# sch_pet.net
KiCad netlist of a schematic drawn in Altium Designer
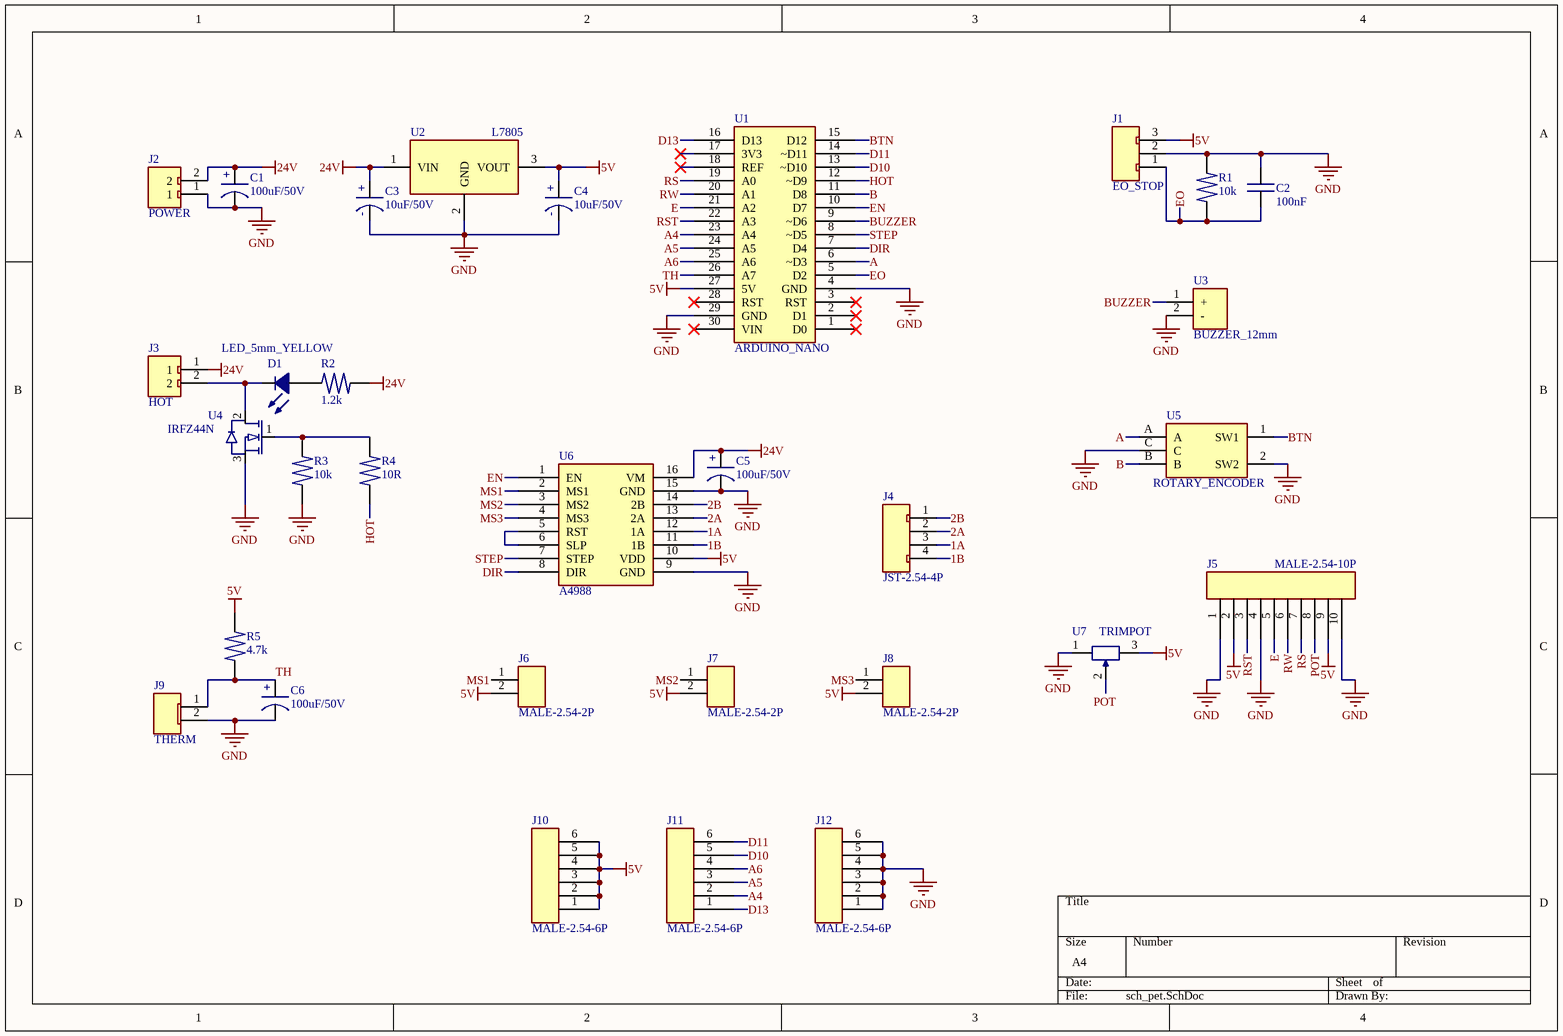
[diagram p0: sch_pet.SchDoc]

(export (version "E")
  (design (tool "Eeschema 10.0.6"))
  (components
    (comp (ref "C1")
      (value "100uF/50V")
      (footprint "100uF/50V")
      (description "Electrolytic Capacitor 100uF/50V")
      (libsource (lib "Electrolytic Capacitor") (part "100uF/50V"))
    )
    (comp (ref "C2")
      (value "100nF")
      (footprint "CAPACITOR 104")
      (description "Ceramic Capacitor 104, 3mm.")
      (libsource (lib "Ceramic Capacitor") (part "CAPACITOR 104"))
    )
    (comp (ref "C3")
      (value "10uF/50V")
      (footprint "10uF/50V")
      (description "Electrolytic Capacitor 10uF/50V")
      (libsource (lib "Electrolytic Capacitor") (part "10uF/50V"))
    )
    (comp (ref "C4")
      (value "10uF/50V")
      (footprint "10uF/50V")
      (description "Electrolytic Capacitor 10uF/50V")
      (libsource (lib "Electrolytic Capacitor") (part "10uF/50V"))
    )
    (comp (ref "C5")
      (value "100uF/50V")
      (footprint "100uF/50V")
      (description "Electrolytic Capacitor 100uF/50V")
      (libsource (lib "Electrolytic Capacitor") (part "100uF/50V"))
    )
    (comp (ref "C6")
      (value "100uF/50V")
      (footprint "100uF/50V")
      (description "Electrolytic Capacitor 100uF/50V")
      (libsource (lib "Electrolytic Capacitor") (part "100uF/50V"))
    )
    (comp (ref "D1")
      (value "LED_5mm_YELLOW")
      (footprint "LED_5mm_YELLOW")
      (description "LED PTH 5mm Yellow.")
      (libsource (lib "LED") (part "LED_5mm_YELLOW"))
    )
    (comp (ref "J1")
      (value "EO_STOP")
      (footprint "JST-2.54-3P")
      (description "Female Connector JST 3 Vias, 2.54mm.")
      (libsource (lib "Connectors") (part "JST-2.54-3P"))
    )
    (comp (ref "J2")
      (value "POWER")
      (footprint "BORNE-5.00-2P")
      (description "Borne 2 Vias, Pitch 5mm.")
      (libsource (lib "Connectors") (part "BORNE-5.00-2P"))
    )
    (comp (ref "J3")
      (value "HOT")
      (footprint "BORNE-5.00-2P")
      (description "Borne 2 Vias, Pitch 5mm.")
      (libsource (lib "") (part "BORNE-5.00-2P_1"))
    )
    (comp (ref "J4")
      (value "JST-2.54-4P")
      (footprint "JST-2.54-4P")
      (description "Female Connector JST 4 Vias, 2.54mm.")
      (libsource (lib "Connectors") (part "JST-2.54-4P"))
    )
    (comp (ref "J5")
      (value "MALE-2.54-10P")
      (footprint "MALE-2.54-10P")
      (description "Male Header Connector 2.54mm 10 Pins.")
      (libsource (lib "Connectors") (part "MALE-2.54-10P"))
    )
    (comp (ref "J6")
      (value "MALE-2.54-2P")
      (footprint "MALE-2.54-2P")
      (description "Male Header Connector 2.54mm 2 Pins.")
      (libsource (lib "Connectors") (part "MALE-2.54-2P"))
    )
    (comp (ref "J7")
      (value "MALE-2.54-2P")
      (footprint "MALE-2.54-2P")
      (description "Male Header Connector 2.54mm 2 Pins.")
      (libsource (lib "Connectors") (part "MALE-2.54-2P"))
    )
    (comp (ref "J8")
      (value "MALE-2.54-2P")
      (footprint "MALE-2.54-2P")
      (description "Male Header Connector 2.54mm 2 Pins.")
      (libsource (lib "Connectors") (part "MALE-2.54-2P"))
    )
    (comp (ref "J9")
      (value "THERM")
      (footprint "JST-2.54-2P")
      (description "Female Connector JST 2 Vias, 2.54mm.")
      (libsource (lib "Connectors") (part "JST-2.54-2P"))
    )
    (comp (ref "J10")
      (value "MALE-2.54-6P")
      (footprint "MALE-2.54-6P")
      (description "Male Header Connector 2.54mm 6 Pins.")
      (libsource (lib "Connectors") (part "MALE-2.54-6P"))
    )
    (comp (ref "J11")
      (value "MALE-2.54-6P")
      (footprint "MALE-2.54-6P")
      (description "Male Header Connector 2.54mm 6 Pins.")
      (libsource (lib "Connectors") (part "MALE-2.54-6P"))
    )
    (comp (ref "J12")
      (value "MALE-2.54-6P")
      (footprint "MALE-2.54-6P")
      (description "Male Header Connector 2.54mm 6 Pins.")
      (libsource (lib "Connectors") (part "MALE-2.54-6P"))
    )
    (comp (ref "R1")
      (value "10k")
      (footprint "RESISTOR_PTH_9.5mm")
      (description "Generic Resistor 9.5mm.")
      (libsource (lib "Resistors") (part "RESISTOR_9.5mm"))
    )
    (comp (ref "R2")
      (value "1.2k")
      (footprint "RESISTOR_PTH_9.5mm")
      (description "Generic Resistor 9.5mm.")
      (libsource (lib "Resistors") (part "RESISTOR_9.5mm"))
    )
    (comp (ref "R3")
      (value "10k")
      (footprint "RESISTOR_PTH_9.5mm")
      (description "Generic Resistor 9.5mm.")
      (libsource (lib "Resistors") (part "RESISTOR_9.5mm"))
    )
    (comp (ref "R4")
      (value "10R")
      (footprint "RESISTOR_PTH_9.5mm")
      (description "Generic Resistor 9.5mm.")
      (libsource (lib "Resistors") (part "RESISTOR_9.5mm"))
    )
    (comp (ref "R5")
      (value "4.7k")
      (footprint "RESISTOR_PTH_9.5mm")
      (description "Generic Resistor 9.5mm.")
      (libsource (lib "Resistors") (part "RESISTOR_9.5mm"))
    )
    (comp (ref "U1")
      (value "ARDUINO_NANO")
      (footprint "ARDUINO_NANO")
      (description "Based on ATmega328P, Clock 16MHz, Flash 32KB, 14 Digital Pins, 8 Analog Pins, 5V, Vin 7-12V.")
      (libsource (lib "Arduino") (part "ARDUINO_NANO"))
    )
    (comp (ref "U2")
      (value "L7805")
      (footprint "L7805_180")
      (description "IC REG LINEAR 5V 1.5A TO220AB")
      (libsource (lib "Voltage Regulators") (part "L7805"))
    )
    (comp (ref "U3")
      (value "BUZZER_12mm")
      (footprint "BUZZER_12mm")
      (description "BUZZER MAGNETIC 12MM")
      (libsource (lib "Random") (part "BUZZER_12mm"))
    )
    (comp (ref "U4")
      (value "IRFZ44N")
      (footprint "IRFZ44N")
      (description "55V N-CHANNEL MOSFET TO-220-3")
      (libsource (lib "Transistors") (part "IRFZ44N"))
    )
    (comp (ref "U5")
      (value "ROTARY_ENCODER")
      (footprint "ROTARY_ENCODER")
      (libsource (lib "Potenciometers") (part "ROTARY_ENCODER"))
    )
    (comp (ref "U6")
      (value "A4988")
      (footprint "A4988")
      (description "Module Stepper Motor Driver 8-35V 2A 20x15mm")
      (libsource (lib "Motor Drivers") (part "A4988"))
    )
    (comp (ref "U7")
      (value "TRIMPOT")
      (footprint "TRIMPOT_1")
      (libsource (lib "Potenciometers") (part "TRIMPOT"))
    )
  )
  (nets
    (net (code "1") (name "/1A") (class "Default")
      (node (ref "J4") (pin "3") (pintype "passive"))
      (node (ref "U6") (pin "12") (pinfunction "1A_12") (pintype "passive"))
    )
    (net (code "2") (name "/1B") (class "Default")
      (node (ref "J4") (pin "4") (pintype "passive"))
      (node (ref "U6") (pin "11") (pinfunction "1B_11") (pintype "passive"))
    )
    (net (code "3") (name "/2A") (class "Default")
      (node (ref "J4") (pin "2") (pintype "passive"))
      (node (ref "U6") (pin "13") (pinfunction "2A_13") (pintype "passive"))
    )
    (net (code "4") (name "/2B") (class "Default")
      (node (ref "J4") (pin "1") (pintype "passive"))
      (node (ref "U6") (pin "14") (pinfunction "2B_14") (pintype "passive"))
    )
    (net (code "5") (name "/A") (class "Default")
      (node (ref "U1") (pin "6") (pinfunction "~D3_6") (pintype "passive"))
      (node (ref "U5") (pin "A") (pinfunction "A_A") (pintype "passive"))
    )
    (net (code "6") (name "/A4") (class "Default")
      (node (ref "J11") (pin "2") (pintype "passive"))
      (node (ref "U1") (pin "23") (pinfunction "A4_23") (pintype "passive"))
    )
    (net (code "7") (name "/A5") (class "Default")
      (node (ref "J11") (pin "3") (pintype "passive"))
      (node (ref "U1") (pin "24") (pinfunction "A5_24") (pintype "passive"))
    )
    (net (code "8") (name "/A6") (class "Default")
      (node (ref "J11") (pin "4") (pintype "passive"))
      (node (ref "U1") (pin "25") (pinfunction "A6_25") (pintype "passive"))
    )
    (net (code "9") (name "/B") (class "Default")
      (node (ref "U1") (pin "11") (pinfunction "D8_11") (pintype "passive"))
      (node (ref "U5") (pin "B") (pinfunction "B_B") (pintype "passive"))
    )
    (net (code "10") (name "/BTN") (class "Default")
      (node (ref "U1") (pin "15") (pinfunction "D12_15") (pintype "passive"))
      (node (ref "U5") (pin "1") (pinfunction "SW1_1") (pintype "passive"))
    )
    (net (code "11") (name "/BUZZER") (class "Default")
      (node (ref "U1") (pin "9") (pinfunction "~D6_9") (pintype "passive"))
      (node (ref "U3") (pin "1") (pinfunction "+_1") (pintype "passive"))
    )
    (net (code "12") (name "/D10") (class "Default")
      (node (ref "J11") (pin "5") (pintype "passive"))
      (node (ref "U1") (pin "13") (pinfunction "~D10_13") (pintype "passive"))
    )
    (net (code "13") (name "/D11") (class "Default")
      (node (ref "J11") (pin "6") (pintype "passive"))
      (node (ref "U1") (pin "14") (pinfunction "~D11_14") (pintype "passive"))
    )
    (net (code "14") (name "/D13") (class "Default")
      (node (ref "J11") (pin "1") (pintype "passive"))
      (node (ref "U1") (pin "16") (pinfunction "D13_16") (pintype "passive"))
    )
    (net (code "15") (name "/DIR") (class "Default")
      (node (ref "U1") (pin "7") (pinfunction "D4_7") (pintype "passive"))
      (node (ref "U6") (pin "8") (pinfunction "DIR_8") (pintype "passive"))
    )
    (net (code "16") (name "/E") (class "Default")
      (node (ref "J5") (pin "5") (pintype "passive"))
      (node (ref "U1") (pin "21") (pinfunction "A2_21") (pintype "passive"))
    )
    (net (code "17") (name "/EN") (class "Default")
      (node (ref "U1") (pin "10") (pinfunction "D7_10") (pintype "passive"))
      (node (ref "U6") (pin "1") (pinfunction "EN_1") (pintype "passive"))
    )
    (net (code "18") (name "/EO") (class "Default")
      (node (ref "C2") (pin "1") (pinfunction "1_1") (pintype "passive"))
      (node (ref "J1") (pin "1") (pintype "passive"))
      (node (ref "R1") (pin "1") (pinfunction "1_1") (pintype "passive"))
      (node (ref "U1") (pin "5") (pinfunction "D2_5") (pintype "passive"))
    )
    (net (code "19") (name "/HOT") (class "Default")
      (node (ref "R4") (pin "1") (pinfunction "1_1") (pintype "passive"))
      (node (ref "U1") (pin "12") (pinfunction "~D9_12") (pintype "passive"))
    )
    (net (code "20") (name "/MS1") (class "Default")
      (node (ref "J6") (pin "1") (pintype "passive"))
      (node (ref "U6") (pin "2") (pinfunction "MS1_2") (pintype "passive"))
    )
    (net (code "21") (name "/MS2") (class "Default")
      (node (ref "J7") (pin "1") (pintype "passive"))
      (node (ref "U6") (pin "3") (pinfunction "MS2_3") (pintype "passive"))
    )
    (net (code "22") (name "/MS3") (class "Default")
      (node (ref "J8") (pin "1") (pintype "passive"))
      (node (ref "U6") (pin "4") (pinfunction "MS3_4") (pintype "passive"))
    )
    (net (code "23") (name "/POT") (class "Default")
      (node (ref "J5") (pin "8") (pintype "passive"))
      (node (ref "U7") (pin "2") (pinfunction "2_2") (pintype "passive"))
    )
    (net (code "24") (name "/RS") (class "Default")
      (node (ref "J5") (pin "7") (pintype "passive"))
      (node (ref "U1") (pin "19") (pinfunction "A0_19") (pintype "passive"))
    )
    (net (code "25") (name "/RST") (class "Default")
      (node (ref "J5") (pin "3") (pintype "passive"))
      (node (ref "U1") (pin "22") (pinfunction "A3_22") (pintype "passive"))
    )
    (net (code "26") (name "/RW") (class "Default")
      (node (ref "J5") (pin "6") (pintype "passive"))
      (node (ref "U1") (pin "20") (pinfunction "A1_20") (pintype "passive"))
    )
    (net (code "27") (name "/STEP") (class "Default")
      (node (ref "U1") (pin "8") (pinfunction "~D5_8") (pintype "passive"))
      (node (ref "U6") (pin "7") (pinfunction "STEP_7") (pintype "passive"))
    )
    (net (code "28") (name "/TH") (class "Default")
      (node (ref "C6") (pin "2") (pinfunction "_2_2") (pintype "passive"))
      (node (ref "J9") (pin "1") (pintype "passive"))
      (node (ref "R5") (pin "1") (pinfunction "1_1") (pintype "passive"))
      (node (ref "U1") (pin "26") (pinfunction "A7_26") (pintype "passive"))
    )
    (net (code "29") (name "5V") (class "Default")
      (node (ref "C4") (pin "2") (pinfunction "_2_2") (pintype "passive"))
      (node (ref "J1") (pin "3") (pintype "passive"))
      (node (ref "J10") (pin "1") (pintype "passive"))
      (node (ref "J10") (pin "2") (pintype "passive"))
      (node (ref "J10") (pin "3") (pintype "passive"))
      (node (ref "J10") (pin "4") (pintype "passive"))
      (node (ref "J10") (pin "5") (pintype "passive"))
      (node (ref "J10") (pin "6") (pintype "passive"))
      (node (ref "J5") (pin "2") (pintype "passive"))
      (node (ref "J5") (pin "9") (pintype "passive"))
      (node (ref "J6") (pin "2") (pintype "passive"))
      (node (ref "J7") (pin "2") (pintype "passive"))
      (node (ref "J8") (pin "2") (pintype "passive"))
      (node (ref "R5") (pin "2") (pinfunction "2_2") (pintype "passive"))
      (node (ref "U1") (pin "27") (pinfunction "5V_27") (pintype "passive"))
      (node (ref "U2") (pin "3") (pinfunction "VOUT_3") (pintype "passive"))
      (node (ref "U6") (pin "10") (pinfunction "VDD_10") (pintype "passive"))
      (node (ref "U7") (pin "3") (pinfunction "3_3") (pintype "passive"))
    )
    (net (code "30") (name "24V") (class "Default")
      (node (ref "C1") (pin "2") (pinfunction "_2_2") (pintype "passive"))
      (node (ref "C3") (pin "2") (pinfunction "_2_2") (pintype "passive"))
      (node (ref "C5") (pin "2") (pinfunction "_2_2") (pintype "passive"))
      (node (ref "J2") (pin "2") (pinfunction "2_2") (pintype "passive"))
      (node (ref "J3") (pin "1") (pinfunction "1_1") (pintype "passive"))
      (node (ref "R2") (pin "2") (pinfunction "2_2") (pintype "passive"))
      (node (ref "U2") (pin "1") (pinfunction "VIN_1") (pintype "passive"))
      (node (ref "U6") (pin "16") (pinfunction "VM_16") (pintype "passive"))
    )
    (net (code "31") (name "GND") (class "Default")
      (node (ref "C1") (pin "1") (pinfunction "1_1") (pintype "passive"))
      (node (ref "C2") (pin "2") (pinfunction "2_2") (pintype "passive"))
      (node (ref "C3") (pin "1") (pinfunction "1_1") (pintype "passive"))
      (node (ref "C4") (pin "1") (pinfunction "1_1") (pintype "passive"))
      (node (ref "C5") (pin "1") (pinfunction "1_1") (pintype "passive"))
      (node (ref "C6") (pin "1") (pinfunction "1_1") (pintype "passive"))
      (node (ref "J1") (pin "2") (pintype "passive"))
      (node (ref "J12") (pin "1") (pintype "passive"))
      (node (ref "J12") (pin "2") (pintype "passive"))
      (node (ref "J12") (pin "3") (pintype "passive"))
      (node (ref "J12") (pin "4") (pintype "passive"))
      (node (ref "J12") (pin "5") (pintype "passive"))
      (node (ref "J12") (pin "6") (pintype "passive"))
      (node (ref "J2") (pin "1") (pinfunction "1_1") (pintype "passive"))
      (node (ref "J5") (pin "1") (pintype "passive"))
      (node (ref "J5") (pin "10") (pintype "passive"))
      (node (ref "J5") (pin "4") (pintype "passive"))
      (node (ref "J9") (pin "2") (pintype "passive"))
      (node (ref "R1") (pin "2") (pinfunction "2_2") (pintype "passive"))
      (node (ref "R3") (pin "1") (pinfunction "1_1") (pintype "passive"))
      (node (ref "U1") (pin "29") (pinfunction "GND_29") (pintype "passive"))
      (node (ref "U1") (pin "4") (pinfunction "GND_4") (pintype "passive"))
      (node (ref "U2") (pin "2") (pinfunction "GND_2") (pintype "passive"))
      (node (ref "U3") (pin "2") (pinfunction "-_2") (pintype "passive"))
      (node (ref "U4") (pin "3") (pinfunction "3_3") (pintype "passive"))
      (node (ref "U5") (pin "2") (pinfunction "SW2_2") (pintype "passive"))
      (node (ref "U5") (pin "C") (pinfunction "C_C") (pintype "passive"))
      (node (ref "U6") (pin "15") (pinfunction "GND_15") (pintype "passive"))
      (node (ref "U6") (pin "9") (pinfunction "GND_9") (pintype "passive"))
      (node (ref "U7") (pin "1") (pinfunction "1_1") (pintype "passive"))
    )
    (net (code "32") (name "Net-(D1-Pad1)") (class "Default")
      (node (ref "D1") (pin "1") (pinfunction "1_1") (pintype "passive"))
      (node (ref "R2") (pin "1") (pinfunction "1_1") (pintype "passive"))
    )
    (net (code "33") (name "Net-(D1-Pad2)") (class "Default")
      (node (ref "D1") (pin "2") (pinfunction "2_2") (pintype "passive"))
      (node (ref "J3") (pin "2") (pinfunction "2_2") (pintype "passive"))
      (node (ref "U4") (pin "2") (pinfunction "2_2") (pintype "passive"))
    )
    (net (code "34") (name "Net-(R3-Pad2)") (class "Default")
      (node (ref "R3") (pin "2") (pinfunction "2_2") (pintype "passive"))
      (node (ref "R4") (pin "2") (pinfunction "2_2") (pintype "passive"))
      (node (ref "U4") (pin "1") (pinfunction "1_1") (pintype "passive"))
    )
    (net (code "35") (name "Net-(U6-RST)") (class "Default")
      (node (ref "U6") (pin "5") (pinfunction "RST_5") (pintype "passive"))
      (node (ref "U6") (pin "6") (pinfunction "SLP_6") (pintype "passive"))
    )
    (net (code "36") (name "unconnected-(U1-3V3-Pad17)") (class "Default")
      (node (ref "U1") (pin "17") (pinfunction "3V3_17") (pintype "passive+no_connect"))
    )
    (net (code "37") (name "unconnected-(U1-D0-Pad1)") (class "Default")
      (node (ref "U1") (pin "1") (pinfunction "D0_1") (pintype "passive+no_connect"))
    )
    (net (code "38") (name "unconnected-(U1-D1-Pad2)") (class "Default")
      (node (ref "U1") (pin "2") (pinfunction "D1_2") (pintype "passive+no_connect"))
    )
    (net (code "39") (name "unconnected-(U1-REF-Pad18)") (class "Default")
      (node (ref "U1") (pin "18") (pinfunction "REF_18") (pintype "passive+no_connect"))
    )
    (net (code "40") (name "unconnected-(U1-RST-Pad3)") (class "Default")
      (node (ref "U1") (pin "3") (pinfunction "RST_3") (pintype "passive+no_connect"))
    )
    (net (code "41") (name "unconnected-(U1-RST-Pad28)") (class "Default")
      (node (ref "U1") (pin "28") (pinfunction "RST_28") (pintype "passive+no_connect"))
    )
    (net (code "42") (name "unconnected-(U1-VIN-Pad30)") (class "Default")
      (node (ref "U1") (pin "30") (pinfunction "VIN_30") (pintype "passive+no_connect"))
    )
  )
)
